# Sheet1.net
KiCad netlist of a schematic drawn in Altium Designer
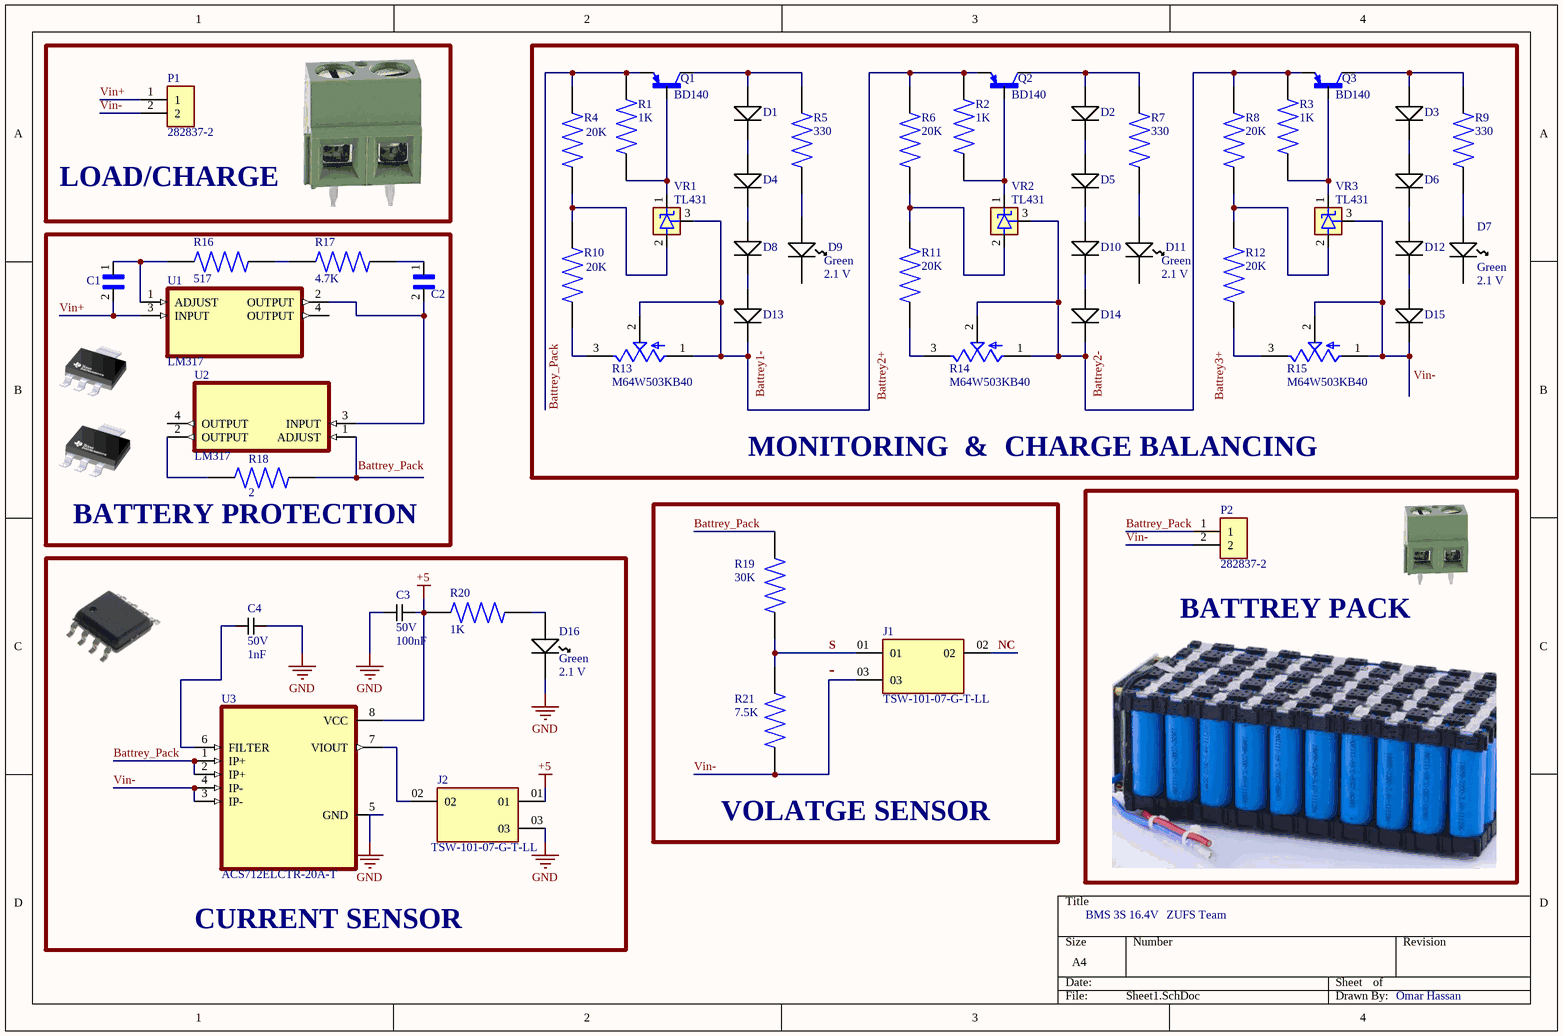
[diagram p0: Sheet1.SchDoc]

(export (version "E")
  (design (tool "Eeschema 10.0.6"))
  (components
    (comp (ref "C1")
      (value "GRM32ER61A107ME20K")
      (footprint "CAPC3225X270N")
      (description "100 ÂµF Â±20% 10V Ceramic Capacitor X5R 1210 (3225 Metric)")
      (fields (field (name "DIGI-KEY_PART_NUMBER") "490-14681-2-ND") (field (name "MF") "Murata Electronics"))
      (libsource (lib "GRM32ER61A107ME20K") (part "GRM32ER61A107ME20K"))
    )
    (comp (ref "C2")
      (value "GRM32ER61A107ME20K")
      (footprint "CAPC3225X270N")
      (description "100 ÂµF Â±20% 10V Ceramic Capacitor X5R 1210 (3225 Metric)")
      (fields (field (name "DIGI-KEY_PART_NUMBER") "490-14681-2-ND") (field (name "MF") "Murata Electronics"))
      (libsource (lib "GRM32ER61A107ME20K") (part "GRM32ER61A107ME20K"))
    )
    (comp (ref "C3")
      (value "100nF Ceramic Multilayer Capacitor_1")
      (footprint "CAPCP2012X09N")
      (description "AVX 0805 Standard 100nF Ceramic Multilayer Capacitor, 50 V dc X7R Dielectric ±10% SMD")
      (fields
        (field (name "MANUFACTURER") "AVX")
        (field (name "VOLTAGE") "50V")
        (field (name "CAPACITANCE") "100nF")
        (field (name "CREATOR") "Ritesh Kanjee")
      )
      (libsource (lib "RS Components - Capacitors") (part "100nF Ceramic Multilayer Capacitor_1"))
    )
    (comp (ref "C4")
      (value "100nF Ceramic Multilayer Capacitor_1")
      (footprint "CAPCP2012X09N")
      (description "AVX 0805 Standard 100nF Ceramic Multilayer Capacitor, 50 V dc X7R Dielectric ±10% SMD")
      (fields
        (field (name "MANUFACTURER") "AVX")
        (field (name "VOLTAGE") "50V")
        (field (name "CAPACITANCE") "1nF")
        (field (name "CREATOR") "Ritesh Kanjee")
      )
      (libsource (lib "RS Components - Capacitors") (part "100nF Ceramic Multilayer Capacitor_1"))
    )
    (comp (ref "D1")
      (value "Panasonic DB2J20900L Schottky Diode, 0.5A, 20V, 2.4ns, 2-Pin SMini2 F5 B")
      (footprint "DIOM1712X07N")
      (fields
        (field (name "MANUFACTURER") "Panasonic")
        (field (name "MANUFACTURER PART NO.") "DB2J20900L")
        (field (name "CREATED BY") "R Kanjee")
      )
      (libsource (lib "Panasonic Diodes") (part "Schottky Diode, 0.5A, 20V, 2.4ns, 2-Pin SMini2 F5 B"))
    )
    (comp (ref "D2")
      (value "Panasonic DB2J20900L Schottky Diode, 0.5A, 20V, 2.4ns, 2-Pin SMini2 F5 B")
      (footprint "DIOM1712X07N")
      (fields
        (field (name "MANUFACTURER") "Panasonic")
        (field (name "MANUFACTURER PART NO.") "DB2J20900L")
        (field (name "CREATED BY") "R Kanjee")
      )
      (libsource (lib "Panasonic Diodes") (part "Schottky Diode, 0.5A, 20V, 2.4ns, 2-Pin SMini2 F5 B"))
    )
    (comp (ref "D3")
      (value "Panasonic DB2J20900L Schottky Diode, 0.5A, 20V, 2.4ns, 2-Pin SMini2 F5 B")
      (footprint "DIOM1712X07N")
      (fields
        (field (name "MANUFACTURER") "Panasonic")
        (field (name "MANUFACTURER PART NO.") "DB2J20900L")
        (field (name "CREATED BY") "R Kanjee")
      )
      (libsource (lib "Panasonic Diodes") (part "Schottky Diode, 0.5A, 20V, 2.4ns, 2-Pin SMini2 F5 B"))
    )
    (comp (ref "D4")
      (value "Panasonic DB2J20900L Schottky Diode, 0.5A, 20V, 2.4ns, 2-Pin SMini2 F5 B")
      (footprint "DIOM1712X07N")
      (fields
        (field (name "MANUFACTURER") "Panasonic")
        (field (name "MANUFACTURER PART NO.") "DB2J20900L")
        (field (name "CREATED BY") "R Kanjee")
      )
      (libsource (lib "Panasonic Diodes") (part "Schottky Diode, 0.5A, 20V, 2.4ns, 2-Pin SMini2 F5 B"))
    )
    (comp (ref "D5")
      (value "Panasonic DB2J20900L Schottky Diode, 0.5A, 20V, 2.4ns, 2-Pin SMini2 F5 B")
      (footprint "DIOM1712X07N")
      (fields
        (field (name "MANUFACTURER") "Panasonic")
        (field (name "MANUFACTURER PART NO.") "DB2J20900L")
        (field (name "CREATED BY") "R Kanjee")
      )
      (libsource (lib "Panasonic Diodes") (part "Schottky Diode, 0.5A, 20V, 2.4ns, 2-Pin SMini2 F5 B"))
    )
    (comp (ref "D6")
      (value "Panasonic DB2J20900L Schottky Diode, 0.5A, 20V, 2.4ns, 2-Pin SMini2 F5 B")
      (footprint "DIOM1712X07N")
      (fields
        (field (name "MANUFACTURER") "Panasonic")
        (field (name "MANUFACTURER PART NO.") "DB2J20900L")
        (field (name "CREATED BY") "R Kanjee")
      )
      (libsource (lib "Panasonic Diodes") (part "Schottky Diode, 0.5A, 20V, 2.4ns, 2-Pin SMini2 F5 B"))
    )
    (comp (ref "D7")
      (value "Kingbright Green LED, 70 mcd 120 ° 0805")
      (footprint "LED1913X12NGREEN")
      (fields
        (field (name "MANUFACTURER") "KingBright")
        (field (name "MANUFACTURER PART NO.") "KP-2012MGC")
        (field (name "COLOR") "Green")
        (field (name "FORWARD VOLTAGE") "2.1 V")
        (field (name "CREATOR") "Ritesh Kanjee")
      )
      (libsource (lib "KingBright LEDs") (part "Kingbright Green LED, 70 mcd 120 ° 0805"))
    )
    (comp (ref "D8")
      (value "Panasonic DB2J20900L Schottky Diode, 0.5A, 20V, 2.4ns, 2-Pin SMini2 F5 B")
      (footprint "DIOM1712X07N")
      (fields
        (field (name "MANUFACTURER") "Panasonic")
        (field (name "MANUFACTURER PART NO.") "DB2J20900L")
        (field (name "CREATED BY") "R Kanjee")
      )
      (libsource (lib "Panasonic Diodes") (part "Schottky Diode, 0.5A, 20V, 2.4ns, 2-Pin SMini2 F5 B"))
    )
    (comp (ref "D9")
      (value "Kingbright Green LED, 70 mcd 120 ° 0805")
      (footprint "LED1913X12NGREEN")
      (fields
        (field (name "MANUFACTURER") "KingBright")
        (field (name "MANUFACTURER PART NO.") "KP-2012MGC")
        (field (name "COLOR") "Green")
        (field (name "FORWARD VOLTAGE") "2.1 V")
        (field (name "CREATOR") "Ritesh Kanjee")
      )
      (libsource (lib "KingBright LEDs") (part "Kingbright Green LED, 70 mcd 120 ° 0805"))
    )
    (comp (ref "D10")
      (value "Panasonic DB2J20900L Schottky Diode, 0.5A, 20V, 2.4ns, 2-Pin SMini2 F5 B")
      (footprint "DIOM1712X07N")
      (fields
        (field (name "MANUFACTURER") "Panasonic")
        (field (name "MANUFACTURER PART NO.") "DB2J20900L")
        (field (name "CREATED BY") "R Kanjee")
      )
      (libsource (lib "Panasonic Diodes") (part "Schottky Diode, 0.5A, 20V, 2.4ns, 2-Pin SMini2 F5 B"))
    )
    (comp (ref "D11")
      (value "Kingbright Green LED, 70 mcd 120 ° 0805")
      (footprint "LED1913X12NGREEN")
      (fields
        (field (name "MANUFACTURER") "KingBright")
        (field (name "MANUFACTURER PART NO.") "KP-2012MGC")
        (field (name "COLOR") "Green")
        (field (name "FORWARD VOLTAGE") "2.1 V")
        (field (name "CREATOR") "Ritesh Kanjee")
      )
      (libsource (lib "KingBright LEDs") (part "Kingbright Green LED, 70 mcd 120 ° 0805"))
    )
    (comp (ref "D12")
      (value "Panasonic DB2J20900L Schottky Diode, 0.5A, 20V, 2.4ns, 2-Pin SMini2 F5 B")
      (footprint "DIOM1712X07N")
      (fields
        (field (name "MANUFACTURER") "Panasonic")
        (field (name "MANUFACTURER PART NO.") "DB2J20900L")
        (field (name "CREATED BY") "R Kanjee")
      )
      (libsource (lib "Panasonic Diodes") (part "Schottky Diode, 0.5A, 20V, 2.4ns, 2-Pin SMini2 F5 B"))
    )
    (comp (ref "D13")
      (value "Panasonic DB2J20900L Schottky Diode, 0.5A, 20V, 2.4ns, 2-Pin SMini2 F5 B")
      (footprint "DIOM1712X07N")
      (fields
        (field (name "MANUFACTURER") "Panasonic")
        (field (name "MANUFACTURER PART NO.") "DB2J20900L")
        (field (name "CREATED BY") "R Kanjee")
      )
      (libsource (lib "Panasonic Diodes") (part "Schottky Diode, 0.5A, 20V, 2.4ns, 2-Pin SMini2 F5 B"))
    )
    (comp (ref "D14")
      (value "Panasonic DB2J20900L Schottky Diode, 0.5A, 20V, 2.4ns, 2-Pin SMini2 F5 B")
      (footprint "DIOM1712X07N")
      (fields
        (field (name "MANUFACTURER") "Panasonic")
        (field (name "MANUFACTURER PART NO.") "DB2J20900L")
        (field (name "CREATED BY") "R Kanjee")
      )
      (libsource (lib "Panasonic Diodes") (part "Schottky Diode, 0.5A, 20V, 2.4ns, 2-Pin SMini2 F5 B"))
    )
    (comp (ref "D15")
      (value "Panasonic DB2J20900L Schottky Diode, 0.5A, 20V, 2.4ns, 2-Pin SMini2 F5 B")
      (footprint "DIOM1712X07N")
      (fields
        (field (name "MANUFACTURER") "Panasonic")
        (field (name "MANUFACTURER PART NO.") "DB2J20900L")
        (field (name "CREATED BY") "R Kanjee")
      )
      (libsource (lib "Panasonic Diodes") (part "Schottky Diode, 0.5A, 20V, 2.4ns, 2-Pin SMini2 F5 B"))
    )
    (comp (ref "D16")
      (value "Kingbright Green LED, 70 mcd 120 ° 0805")
      (footprint "LED1913X12NGREEN")
      (fields
        (field (name "MANUFACTURER") "KingBright")
        (field (name "MANUFACTURER PART NO.") "KP-2012MGC")
        (field (name "COLOR") "Green")
        (field (name "FORWARD VOLTAGE") "2.1 V")
        (field (name "CREATOR") "Ritesh Kanjee")
      )
      (libsource (lib "KingBright LEDs") (part "Kingbright Green LED, 70 mcd 120 ° 0805"))
    )
    (comp (ref "J1")
      (value "TSW-101-07-G-T-LL")
      (footprint "SAMTEC_TSW-101-07-G-T-LL")
      (libsource (lib "TSW-101-07-G-T-LL") (part "TSW-101-07-G-T-LL"))
    )
    (comp (ref "J2")
      (value "TSW-101-07-G-T-LL")
      (footprint "SAMTEC_TSW-101-07-G-T-LL")
      (libsource (lib "") (part "TSW-101-07-G-T-LL_1"))
    )
    (comp (ref "P1")
      (value "282837-2")
      (footprint "TE_282837-2")
      (fields (field (name "MF") "TE Connectivity"))
      (libsource (lib "282837-2") (part "282837-2"))
    )
    (comp (ref "P2")
      (value "282837-2")
      (footprint "TE_282837-2")
      (fields (field (name "MF") "TE Connectivity"))
      (libsource (lib "282837-2") (part "282837-2"))
    )
    (comp (ref "Q1")
      (value "BD140")
      (footprint "TO229P760X270X1364-3")
      (description "Bipolar (BJT) Transistor PNP 80 V 1.5 A - 1.25 W Through Hole TO-126-3")
      (fields (field (name "MF") "ON Semiconductor"))
      (libsource (lib "BD140") (part "BD140"))
    )
    (comp (ref "Q2")
      (value "BD140")
      (footprint "TO229P760X270X1364-3")
      (description "Bipolar (BJT) Transistor PNP 80 V 1.5 A - 1.25 W Through Hole TO-126-3")
      (fields (field (name "MF") "ON Semiconductor"))
      (libsource (lib "BD140") (part "BD140"))
    )
    (comp (ref "Q3")
      (value "BD140")
      (footprint "TO229P760X270X1364-3")
      (description "Bipolar (BJT) Transistor PNP 80 V 1.5 A - 1.25 W Through Hole TO-126-3")
      (fields (field (name "MF") "ON Semiconductor"))
      (libsource (lib "BD140") (part "BD140"))
    )
    (comp (ref "R1")
      (value "1K")
      (footprint "RESC3115X65N")
      (description "Fixed Resistor CRGP 1206 1K5 1%")
      (fields (field (name "MP") "CRGP1206F1K5") (field (name "DIGI-KEY_PART_NUMBER") "A130540CT-ND"))
      (libsource (lib "CRGP1206F1K5") (part "CRGP1206F1K5"))
    )
    (comp (ref "R2")
      (value "1K")
      (footprint "RESC3115X65N")
      (description "Fixed Resistor CRGP 1206 1K5 1%")
      (fields (field (name "MP") "CRGP1206F1K5") (field (name "DIGI-KEY_PART_NUMBER") "A130540CT-ND"))
      (libsource (lib "CRGP1206F1K5") (part "CRGP1206F1K5"))
    )
    (comp (ref "R3")
      (value "1K")
      (footprint "RESC3115X65N")
      (description "Fixed Resistor CRGP 1206 1K5 1%")
      (fields (field (name "MP") "CRGP1206F1K5") (field (name "DIGI-KEY_PART_NUMBER") "A130540CT-ND"))
      (libsource (lib "CRGP1206F1K5") (part "CRGP1206F1K5"))
    )
    (comp (ref "R4")
      (value "20K")
      (footprint "RESC3115X65N")
      (description "Fixed Resistor CRGP 1206 1K5 1%")
      (fields (field (name "MP") "CRGP1206F1K5") (field (name "DIGI-KEY_PART_NUMBER") "A130540CT-ND"))
      (libsource (lib "CRGP1206F1K5") (part "CRGP1206F1K5"))
    )
    (comp (ref "R5")
      (value "330")
      (footprint "RESC3115X65N")
      (description "Fixed Resistor CRGP 1206 1K5 1%")
      (fields (field (name "MP") "CRGP1206F1K5") (field (name "DIGI-KEY_PART_NUMBER") "A130540CT-ND"))
      (libsource (lib "CRGP1206F1K5") (part "CRGP1206F1K5"))
    )
    (comp (ref "R6")
      (value "20K")
      (footprint "RESC3115X65N")
      (description "Fixed Resistor CRGP 1206 1K5 1%")
      (fields (field (name "MP") "CRGP1206F1K5") (field (name "DIGI-KEY_PART_NUMBER") "A130540CT-ND"))
      (libsource (lib "CRGP1206F1K5") (part "CRGP1206F1K5"))
    )
    (comp (ref "R7")
      (value "330")
      (footprint "RESC3115X65N")
      (description "Fixed Resistor CRGP 1206 1K5 1%")
      (fields (field (name "MP") "CRGP1206F1K5") (field (name "DIGI-KEY_PART_NUMBER") "A130540CT-ND"))
      (libsource (lib "CRGP1206F1K5") (part "CRGP1206F1K5"))
    )
    (comp (ref "R8")
      (value "20K")
      (footprint "RESC3115X65N")
      (description "Fixed Resistor CRGP 1206 1K5 1%")
      (fields (field (name "MP") "CRGP1206F1K5") (field (name "DIGI-KEY_PART_NUMBER") "A130540CT-ND"))
      (libsource (lib "CRGP1206F1K5") (part "CRGP1206F1K5"))
    )
    (comp (ref "R9")
      (value "330")
      (footprint "RESC3115X65N")
      (description "Fixed Resistor CRGP 1206 1K5 1%")
      (fields (field (name "MP") "CRGP1206F1K5") (field (name "DIGI-KEY_PART_NUMBER") "A130540CT-ND"))
      (libsource (lib "CRGP1206F1K5") (part "CRGP1206F1K5"))
    )
    (comp (ref "R10")
      (value "20K")
      (footprint "RESC3115X65N")
      (description "Fixed Resistor CRGP 1206 1K5 1%")
      (fields (field (name "MP") "CRGP1206F1K5") (field (name "DIGI-KEY_PART_NUMBER") "A130540CT-ND"))
      (libsource (lib "CRGP1206F1K5") (part "CRGP1206F1K5"))
    )
    (comp (ref "R11")
      (value "20K")
      (footprint "RESC3115X65N")
      (description "Fixed Resistor CRGP 1206 1K5 1%")
      (fields (field (name "MP") "CRGP1206F1K5") (field (name "DIGI-KEY_PART_NUMBER") "A130540CT-ND"))
      (libsource (lib "CRGP1206F1K5") (part "CRGP1206F1K5"))
    )
    (comp (ref "R12")
      (value "20K")
      (footprint "RESC3115X65N")
      (description "Fixed Resistor CRGP 1206 1K5 1%")
      (fields (field (name "MP") "CRGP1206F1K5") (field (name "DIGI-KEY_PART_NUMBER") "A130540CT-ND"))
      (libsource (lib "CRGP1206F1K5") (part "CRGP1206F1K5"))
    )
    (comp (ref "R13")
      (value "M64W503KB40")
      (footprint "SIP460W50P254L970H980Q3P")
      (description "50 kOhms 0.5W, 1/2W PC Pins Through Hole Trimmer Potentiometer Cermet 21.0 Turn Top Adjustment")
      (fields (field (name "MF") "Vishay"))
      (libsource (lib "M64W503KB40") (part "M64W503KB40"))
    )
    (comp (ref "R14")
      (value "M64W503KB40")
      (footprint "SIP460W50P254L970H980Q3P")
      (description "50 kOhms 0.5W, 1/2W PC Pins Through Hole Trimmer Potentiometer Cermet 21.0 Turn Top Adjustment")
      (fields (field (name "MF") "Vishay"))
      (libsource (lib "M64W503KB40") (part "M64W503KB40"))
    )
    (comp (ref "R15")
      (value "M64W503KB40")
      (footprint "SIP460W50P254L970H980Q3P")
      (description "50 kOhms 0.5W, 1/2W PC Pins Through Hole Trimmer Potentiometer Cermet 21.0 Turn Top Adjustment")
      (fields (field (name "MF") "Vishay"))
      (libsource (lib "M64W503KB40") (part "M64W503KB40"))
    )
    (comp (ref "R16")
      (value "517")
      (footprint "RESC3115X65N")
      (description "Fixed Resistor CRGP 1206 1K5 1%")
      (fields (field (name "MP") "CRGP1206F1K5") (field (name "DIGI-KEY_PART_NUMBER") "A130540CT-ND"))
      (libsource (lib "CRGP1206F1K5") (part "CRGP1206F1K5"))
    )
    (comp (ref "R17")
      (value "4.7K")
      (footprint "RESC3115X65N")
      (description "Fixed Resistor CRGP 1206 1K5 1%")
      (fields (field (name "MP") "CRGP1206F1K5") (field (name "DIGI-KEY_PART_NUMBER") "A130540CT-ND"))
      (libsource (lib "CRGP1206F1K5") (part "CRGP1206F1K5"))
    )
    (comp (ref "R18")
      (value "2")
      (footprint "RESC3115X65N")
      (description "Fixed Resistor CRGP 1206 1K5 1%")
      (fields (field (name "MP") "CRGP1206F1K5") (field (name "DIGI-KEY_PART_NUMBER") "A130540CT-ND"))
      (libsource (lib "CRGP1206F1K5") (part "CRGP1206F1K5"))
    )
    (comp (ref "R19")
      (value "30K")
      (footprint "RESC3115X65N")
      (description "Fixed Resistor CRGP 1206 1K5 1%")
      (fields (field (name "MP") "CRGP1206F1K5") (field (name "DIGI-KEY_PART_NUMBER") "A130540CT-ND"))
      (libsource (lib "CRGP1206F1K5") (part "CRGP1206F1K5"))
    )
    (comp (ref "R20")
      (value "1K")
      (footprint "RESC3115X65N")
      (description "Fixed Resistor CRGP 1206 1K5 1%")
      (fields (field (name "MP") "CRGP1206F1K5") (field (name "DIGI-KEY_PART_NUMBER") "A130540CT-ND"))
      (libsource (lib "CRGP1206F1K5") (part "CRGP1206F1K5"))
    )
    (comp (ref "R21")
      (value "7.5K")
      (footprint "RESC3115X65N")
      (description "Fixed Resistor CRGP 1206 1K5 1%")
      (fields (field (name "MP") "CRGP1206F1K5") (field (name "DIGI-KEY_PART_NUMBER") "A130540CT-ND"))
      (libsource (lib "CRGP1206F1K5") (part "CRGP1206F1K5"))
    )
    (comp (ref "U1")
      (value "LM317")
      (footprint "SOT230P700X180-4N")
      (description "1.5-A, 40-V, adjustable linear voltage regulator 4-SOT-223 0 to 125")
      (fields (field (name "MP") "LM317DCYG3") (field (name "MF") "Texas Instruments"))
      (libsource (lib "") (part "LM317DCYG3_1"))
    )
    (comp (ref "U2")
      (value "LM317")
      (footprint "SOT230P700X180-4N")
      (description "1.5-A, 40-V, adjustable linear voltage regulator 4-SOT-223 0 to 125")
      (fields (field (name "MP") "LM317DCYG3") (field (name "MF") "Texas Instruments"))
      (libsource (lib "LM317DCYG3") (part "LM317DCYG3"))
    )
    (comp (ref "U3")
      (value "ACS712ELCTR-20A-T")
      (footprint "SOIC127P600X175-8N")
      (description "Current Sensor 20A 1 Channel Hall Effect, Open Loop Bidirectional 8-SOIC (0.154, 3.90mm Width)")
      (fields (field (name "MF") "Allegro"))
      (libsource (lib "ACS712ELCTR-20A-T") (part "ACS712ELCTR-20A-T"))
    )
    (comp (ref "VR1")
      (value "TL431")
      (footprint "VREG_TL431CLP")
      (description "Adjustable precision shunt regulator")
      (fields (field (name "MF") "Texas Instruments") (field (name "MP") "TL431CLP"))
      (libsource (lib "TL431CLP") (part "TL431CLP"))
    )
    (comp (ref "VR2")
      (value "TL431")
      (footprint "VREG_TL431CLP")
      (description "Adjustable precision shunt regulator")
      (fields (field (name "MF") "Texas Instruments") (field (name "MP") "TL431CLP"))
      (libsource (lib "TL431CLP") (part "TL431CLP"))
    )
    (comp (ref "VR3")
      (value "TL431")
      (footprint "VREG_TL431CLP")
      (description "Adjustable precision shunt regulator")
      (fields (field (name "MF") "Texas Instruments") (field (name "MP") "TL431CLP"))
      (libsource (lib "TL431CLP") (part "TL431CLP"))
    )
  )
  (nets
    (net (code "1") (name "+5") (class "Default")
      (node (ref "C3") (pin "2") (pinfunction "2_2") (pintype "passive"))
      (node (ref "J2") (pin "01") (pinfunction "01_01") (pintype "passive"))
      (node (ref "R20") (pin "2") (pinfunction "2_2") (pintype "passive"))
      (node (ref "U3") (pin "8") (pinfunction "VCC_8") (pintype "power_in"))
    )
    (net (code "2") (name "/-") (class "Default")
      (node (ref "J1") (pin "03") (pinfunction "03_03") (pintype "passive"))
      (node (ref "P1") (pin "2") (pinfunction "2_2") (pintype "passive"))
      (node (ref "P2") (pin "2") (pinfunction "2_2") (pintype "passive"))
      (node (ref "R21") (pin "1") (pinfunction "1_1") (pintype "passive"))
      (node (ref "U3") (pin "3") (pinfunction "IP-_3") (pintype "input"))
      (node (ref "U3") (pin "4") (pinfunction "IP-_4") (pintype "input"))
    )
    (net (code "7") (name "/Battrey_Pack") (class "Default")
      (node (ref "P2") (pin "1") (pinfunction "1_1") (pintype "passive"))
      (node (ref "Q1") (pin "1") (pinfunction "E_1") (pintype "passive"))
      (node (ref "R1") (pin "2") (pinfunction "2_2") (pintype "passive"))
      (node (ref "R19") (pin "2") (pinfunction "2_2") (pintype "passive"))
      (node (ref "R4") (pin "2") (pinfunction "2_2") (pintype "passive"))
      (node (ref "U3") (pin "1") (pinfunction "IP+_1") (pintype "input"))
      (node (ref "U3") (pin "2") (pinfunction "IP+_2") (pintype "input"))
    )
    (net (code "8") (name "/NC") (class "Default")
      (node (ref "J1") (pin "02") (pinfunction "02_02") (pintype "passive"))
    )
    (net (code "9") (name "/S") (class "Default")
      (node (ref "J1") (pin "01") (pinfunction "01_01") (pintype "passive"))
      (node (ref "R19") (pin "1") (pinfunction "1_1") (pintype "passive"))
      (node (ref "R21") (pin "2") (pinfunction "2_2") (pintype "passive"))
    )
    (net (code "10") (name "/Vin+") (class "Default")
      (node (ref "C1") (pin "2") (pinfunction "2_2") (pintype "passive"))
      (node (ref "P1") (pin "1") (pinfunction "1_1") (pintype "passive"))
      (node (ref "U1") (pin "3") (pinfunction "INPUT_3") (pintype "input"))
    )
    (net (code "11") (name "GND") (class "Default")
      (node (ref "C3") (pin "1") (pinfunction "1_1") (pintype "passive"))
      (node (ref "C4") (pin "2") (pinfunction "2_2") (pintype "passive"))
      (node (ref "D16") (pin "2") (pinfunction "K_2") (pintype "passive"))
      (node (ref "J2") (pin "03") (pinfunction "03_03") (pintype "passive"))
      (node (ref "U3") (pin "5") (pinfunction "GND_5") (pintype "power_in"))
    )
    (net (code "12") (name "Net-(C2-Pad1)") (class "Default")
      (node (ref "C2") (pin "1") (pinfunction "1_1") (pintype "passive"))
      (node (ref "R17") (pin "1") (pinfunction "1_1") (pintype "passive"))
    )
    (net (code "13") (name "Net-(D1-Pad1)") (class "Default")
      (node (ref "D1") (pin "1") (pinfunction "1_1") (pintype "passive"))
      (node (ref "D4") (pin "2") (pinfunction "2_2") (pintype "passive"))
    )
    (net (code "14") (name "Net-(D2-Pad1)") (class "Default")
      (node (ref "D2") (pin "1") (pinfunction "1_1") (pintype "passive"))
      (node (ref "D5") (pin "2") (pinfunction "2_2") (pintype "passive"))
    )
    (net (code "15") (name "Net-(D3-Pad1)") (class "Default")
      (node (ref "D3") (pin "1") (pinfunction "1_1") (pintype "passive"))
      (node (ref "D6") (pin "2") (pinfunction "2_2") (pintype "passive"))
    )
    (net (code "16") (name "Net-(D4-Pad1)") (class "Default")
      (node (ref "D4") (pin "1") (pinfunction "1_1") (pintype "passive"))
      (node (ref "D8") (pin "2") (pinfunction "2_2") (pintype "passive"))
    )
    (net (code "17") (name "Net-(D7-A)") (class "Default")
      (node (ref "D7") (pin "1") (pinfunction "A_1") (pintype "passive"))
      (node (ref "R9") (pin "1") (pinfunction "1_1") (pintype "passive"))
    )
    (net (code "18") (name "Net-(D9-A)") (class "Default")
      (node (ref "D9") (pin "1") (pinfunction "A_1") (pintype "passive"))
      (node (ref "R5") (pin "1") (pinfunction "1_1") (pintype "passive"))
    )
    (net (code "19") (name "Net-(D10-Pad1)") (class "Default")
      (node (ref "D10") (pin "1") (pinfunction "1_1") (pintype "passive"))
      (node (ref "D14") (pin "2") (pinfunction "2_2") (pintype "passive"))
    )
    (net (code "20") (name "Net-(D10-Pad2)") (class "Default")
      (node (ref "D10") (pin "2") (pinfunction "2_2") (pintype "passive"))
      (node (ref "D5") (pin "1") (pinfunction "1_1") (pintype "passive"))
    )
    (net (code "21") (name "Net-(D11-A)") (class "Default")
      (node (ref "D11") (pin "1") (pinfunction "A_1") (pintype "passive"))
      (node (ref "R7") (pin "1") (pinfunction "1_1") (pintype "passive"))
    )
    (net (code "22") (name "Net-(D12-Pad1)") (class "Default")
      (node (ref "D12") (pin "1") (pinfunction "1_1") (pintype "passive"))
      (node (ref "D15") (pin "2") (pinfunction "2_2") (pintype "passive"))
    )
    (net (code "23") (name "Net-(D12-Pad2)") (class "Default")
      (node (ref "D12") (pin "2") (pinfunction "2_2") (pintype "passive"))
      (node (ref "D6") (pin "1") (pinfunction "1_1") (pintype "passive"))
    )
    (net (code "24") (name "Net-(D13-Pad2)") (class "Default")
      (node (ref "D13") (pin "2") (pinfunction "2_2") (pintype "passive"))
      (node (ref "D8") (pin "1") (pinfunction "1_1") (pintype "passive"))
    )
    (net (code "25") (name "Net-(D16-A)") (class "Default")
      (node (ref "D16") (pin "1") (pinfunction "A_1") (pintype "passive"))
      (node (ref "R20") (pin "1") (pinfunction "1_1") (pintype "passive"))
    )
    (net (code "26") (name "Net-(Q1-B)") (class "Default")
      (node (ref "Q1") (pin "3") (pinfunction "B_3") (pintype "passive"))
      (node (ref "R1") (pin "1") (pinfunction "1_1") (pintype "passive"))
      (node (ref "VR1") (pin "1") (pinfunction "CATHODE_1") (pintype "passive"))
    )
    (net (code "27") (name "Net-(Q1-C)") (class "Default")
      (node (ref "D1") (pin "2") (pinfunction "2_2") (pintype "passive"))
      (node (ref "Q1") (pin "2") (pinfunction "C_2") (pintype "passive"))
      (node (ref "R5") (pin "2") (pinfunction "2_2") (pintype "passive"))
    )
    (net (code "28") (name "Net-(Q2-B)") (class "Default")
      (node (ref "Q2") (pin "3") (pinfunction "B_3") (pintype "passive"))
      (node (ref "R2") (pin "1") (pinfunction "1_1") (pintype "passive"))
      (node (ref "VR2") (pin "1") (pinfunction "CATHODE_1") (pintype "passive"))
    )
    (net (code "29") (name "Net-(Q2-C)") (class "Default")
      (node (ref "D2") (pin "2") (pinfunction "2_2") (pintype "passive"))
      (node (ref "Q2") (pin "2") (pinfunction "C_2") (pintype "passive"))
      (node (ref "R7") (pin "2") (pinfunction "2_2") (pintype "passive"))
    )
    (net (code "30") (name "Net-(Q2-E)") (class "Default")
      (node (ref "D13") (pin "1") (pinfunction "1_1") (pintype "passive"))
      (node (ref "Q2") (pin "1") (pinfunction "E_1") (pintype "passive"))
      (node (ref "R13") (pin "1") (pinfunction "A_1") (pintype "passive"))
      (node (ref "R13") (pin "2") (pinfunction "B_2") (pintype "passive"))
      (node (ref "R2") (pin "2") (pinfunction "2_2") (pintype "passive"))
      (node (ref "R6") (pin "2") (pinfunction "2_2") (pintype "passive"))
      (node (ref "VR1") (pin "3") (pinfunction "REF_3") (pintype "passive"))
    )
    (net (code "31") (name "Net-(Q3-B)") (class "Default")
      (node (ref "Q3") (pin "3") (pinfunction "B_3") (pintype "passive"))
      (node (ref "R3") (pin "1") (pinfunction "1_1") (pintype "passive"))
      (node (ref "VR3") (pin "1") (pinfunction "CATHODE_1") (pintype "passive"))
    )
    (net (code "32") (name "Net-(Q3-C)") (class "Default")
      (node (ref "D3") (pin "2") (pinfunction "2_2") (pintype "passive"))
      (node (ref "Q3") (pin "2") (pinfunction "C_2") (pintype "passive"))
      (node (ref "R9") (pin "2") (pinfunction "2_2") (pintype "passive"))
    )
    (net (code "33") (name "Net-(Q3-E)") (class "Default")
      (node (ref "D14") (pin "1") (pinfunction "1_1") (pintype "passive"))
      (node (ref "Q3") (pin "1") (pinfunction "E_1") (pintype "passive"))
      (node (ref "R14") (pin "1") (pinfunction "A_1") (pintype "passive"))
      (node (ref "R14") (pin "2") (pinfunction "B_2") (pintype "passive"))
      (node (ref "R3") (pin "2") (pinfunction "2_2") (pintype "passive"))
      (node (ref "R8") (pin "2") (pinfunction "2_2") (pintype "passive"))
      (node (ref "VR2") (pin "3") (pinfunction "REF_3") (pintype "passive"))
    )
    (net (code "34") (name "Net-(R13-C)") (class "Default")
      (node (ref "R10") (pin "1") (pinfunction "1_1") (pintype "passive"))
      (node (ref "R13") (pin "3") (pinfunction "C_3") (pintype "passive"))
    )
    (net (code "35") (name "Net-(R14-C)") (class "Default")
      (node (ref "R11") (pin "1") (pinfunction "1_1") (pintype "passive"))
      (node (ref "R14") (pin "3") (pinfunction "C_3") (pintype "passive"))
    )
    (net (code "36") (name "Net-(R15-A)") (class "Default")
      (node (ref "D15") (pin "1") (pinfunction "1_1") (pintype "passive"))
      (node (ref "R15") (pin "1") (pinfunction "A_1") (pintype "passive"))
      (node (ref "R15") (pin "2") (pinfunction "B_2") (pintype "passive"))
      (node (ref "VR3") (pin "3") (pinfunction "REF_3") (pintype "passive"))
    )
    (net (code "37") (name "Net-(R15-C)") (class "Default")
      (node (ref "R12") (pin "1") (pinfunction "1_1") (pintype "passive"))
      (node (ref "R15") (pin "3") (pinfunction "C_3") (pintype "passive"))
    )
    (net (code "38") (name "Net-(R16-Pad1)") (class "Default")
      (node (ref "R16") (pin "1") (pinfunction "1_1") (pintype "passive"))
      (node (ref "R17") (pin "2") (pinfunction "2_2") (pintype "passive"))
    )
    (net (code "39") (name "Net-(R18-Pad2)") (class "Default")
      (node (ref "R18") (pin "2") (pinfunction "2_2") (pintype "passive"))
      (node (ref "U2") (pin "2") (pinfunction "OUTPUT_2") (pintype "output"))
    )
    (net (code "40") (name "Net-(U1-ADJUST)") (class "Default")
      (node (ref "C1") (pin "1") (pinfunction "1_1") (pintype "passive"))
      (node (ref "R16") (pin "2") (pinfunction "2_2") (pintype "passive"))
      (node (ref "U1") (pin "1") (pinfunction "ADJUST_1") (pintype "input"))
    )
    (net (code "41") (name "Net-(U2-ADJUST)") (class "Default")
      (node (ref "R18") (pin "1") (pinfunction "1_1") (pintype "passive"))
      (node (ref "U2") (pin "1") (pinfunction "ADJUST_1") (pintype "input"))
    )
    (net (code "42") (name "Net-(U2-INPUT)") (class "Default")
      (node (ref "C2") (pin "2") (pinfunction "2_2") (pintype "passive"))
      (node (ref "U1") (pin "2") (pinfunction "OUTPUT_2") (pintype "output"))
      (node (ref "U2") (pin "3") (pinfunction "INPUT_3") (pintype "input"))
    )
    (net (code "43") (name "Net-(U3-FILTER)") (class "Default")
      (node (ref "C4") (pin "1") (pinfunction "1_1") (pintype "passive"))
      (node (ref "U3") (pin "6") (pinfunction "FILTER_6") (pintype "input"))
    )
    (net (code "44") (name "Net-(U3-VIOUT)") (class "Default")
      (node (ref "J2") (pin "02") (pinfunction "02_02") (pintype "passive"))
      (node (ref "U3") (pin "7") (pinfunction "VIOUT_7") (pintype "output"))
    )
    (net (code "45") (name "Net-(VR1-ANODE)") (class "Default")
      (node (ref "R10") (pin "2") (pinfunction "2_2") (pintype "passive"))
      (node (ref "R4") (pin "1") (pinfunction "1_1") (pintype "passive"))
      (node (ref "VR1") (pin "2") (pinfunction "ANODE_2") (pintype "passive"))
    )
    (net (code "46") (name "Net-(VR2-ANODE)") (class "Default")
      (node (ref "R11") (pin "2") (pinfunction "2_2") (pintype "passive"))
      (node (ref "R6") (pin "1") (pinfunction "1_1") (pintype "passive"))
      (node (ref "VR2") (pin "2") (pinfunction "ANODE_2") (pintype "passive"))
    )
    (net (code "47") (name "Net-(VR3-ANODE)") (class "Default")
      (node (ref "R12") (pin "2") (pinfunction "2_2") (pintype "passive"))
      (node (ref "R8") (pin "1") (pinfunction "1_1") (pintype "passive"))
      (node (ref "VR3") (pin "2") (pinfunction "ANODE_2") (pintype "passive"))
    )
    (net (code "48") (name "unconnected-(D7-K-Pad2)") (class "Default")
      (node (ref "D7") (pin "2") (pinfunction "K_2") (pintype "passive"))
    )
    (net (code "49") (name "unconnected-(D9-K-Pad2)") (class "Default")
      (node (ref "D9") (pin "2") (pinfunction "K_2") (pintype "passive"))
    )
    (net (code "50") (name "unconnected-(D11-K-Pad2)") (class "Default")
      (node (ref "D11") (pin "2") (pinfunction "K_2") (pintype "passive"))
    )
    (net (code "51") (name "unconnected-(U1-OUTPUT-Pad4)") (class "Default")
      (node (ref "U1") (pin "4") (pinfunction "OUTPUT_4") (pintype "output"))
    )
    (net (code "52") (name "unconnected-(U2-OUTPUT-Pad4)") (class "Default")
      (node (ref "U2") (pin "4") (pinfunction "OUTPUT_4") (pintype "output"))
    )
  )
)
